# 0_3b.net
KiCad netlist of a schematic drawn in EAGLE
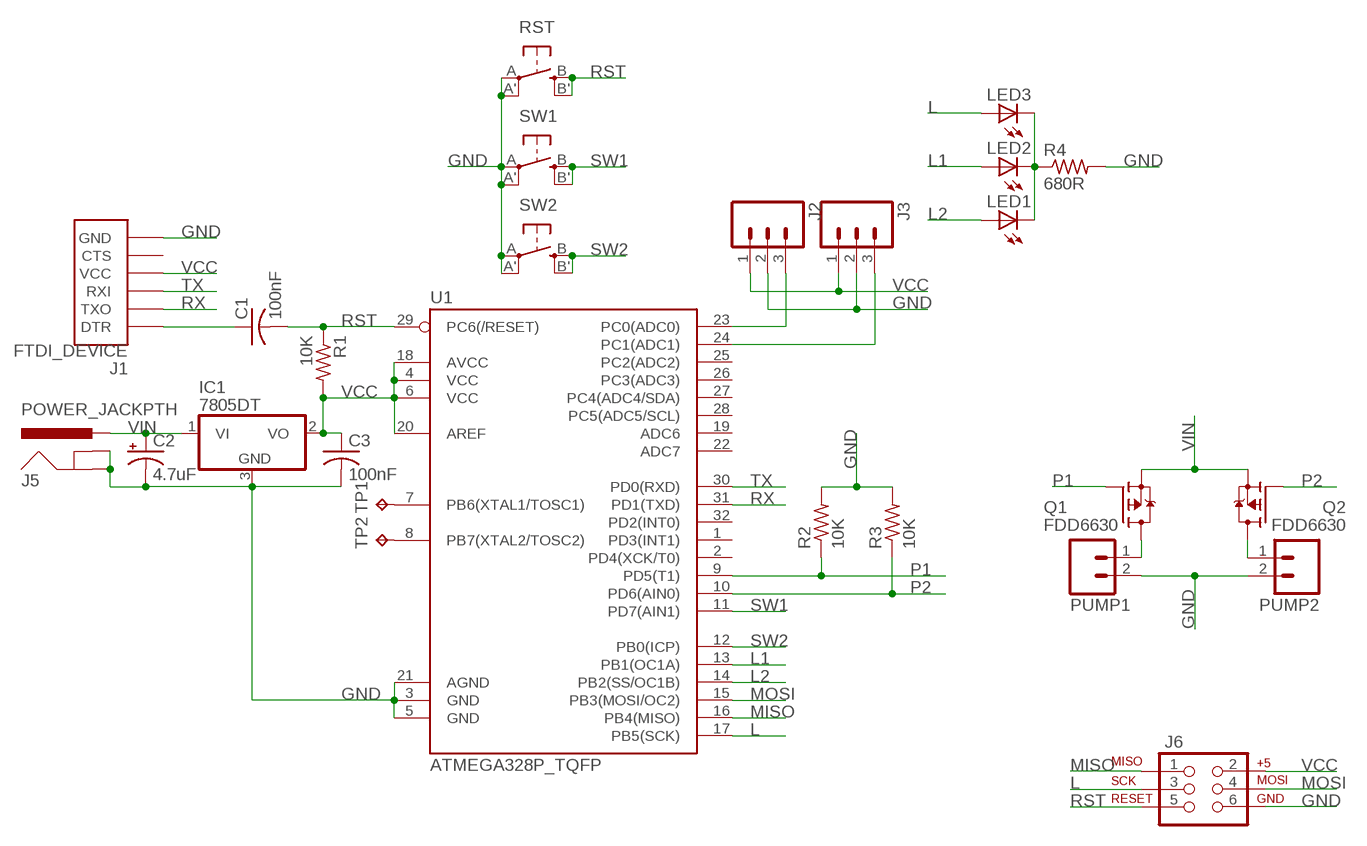
[diagram p0: schematic, sheet 1]

(export (version "E")
  (design (tool "Eeschema 10.0.6"))
  (components
    (comp (ref "C1")
      (value "100nF")
      (footprint "eagle-import:C1206K")
      (libsource (lib "eagle-import") (part "resistor_C-USC1206K"))
    )
    (comp (ref "C2")
      (value "4.7uF")
      (footprint "eagle-import:153CLV-0405")
      (libsource (lib "eagle-import") (part "CPOL-US153CLV-0405"))
    )
    (comp (ref "C3")
      (value "100nF")
      (footprint "eagle-import:C1206K")
      (libsource (lib "eagle-import") (part "C-USC1206K"))
    )
    (comp (ref "IC1")
      (value "7805DT")
      (footprint "eagle-import:TO252")
      (libsource (lib "eagle-import") (part "78DT05"))
    )
    (comp (ref "J1")
      (value "FTDI_DEVICE")
      (footprint "eagle-import:FTDI_DEVICE_SIDE")
      (libsource (lib "eagle-import") (part "FTDI_DEVICE"))
    )
    (comp (ref "J2")
      (value "M03PTH")
      (footprint "eagle-import:1X03")
      (libsource (lib "eagle-import") (part "M03PTH"))
    )
    (comp (ref "J3")
      (value "M03PTH")
      (footprint "eagle-import:1X03")
      (libsource (lib "eagle-import") (part "M03PTH"))
    )
    (comp (ref "J5")
      (value "POWER_JACKPTH")
      (footprint "eagle-import:POWER_JACK_PTH")
      (libsource (lib "eagle-import") (part "POWER_JACKPTH"))
    )
    (comp (ref "J6")
      (value "AVR_SPI_PRG_6PTH")
      (footprint "eagle-import:2X3")
      (libsource (lib "eagle-import") (part "AVR_SPI_PRG_6PTH"))
    )
    (comp (ref "LED1")
      (value "LED3MM")
      (footprint "eagle-import:LED3MM")
      (libsource (lib "eagle-import") (part "LED3MM"))
    )
    (comp (ref "LED2")
      (value "LED3MM")
      (footprint "eagle-import:LED3MM")
      (libsource (lib "eagle-import") (part "LED3MM"))
    )
    (comp (ref "LED3")
      (value "LED3MM")
      (footprint "eagle-import:LED3MM")
      (libsource (lib "eagle-import") (part "LED3MM"))
    )
    (comp (ref "PUMP1")
      (value "M02PTH")
      (footprint "eagle-import:1X02")
      (libsource (lib "eagle-import") (part "M02PTH"))
    )
    (comp (ref "PUMP2")
      (value "M02PTH")
      (footprint "eagle-import:1X02")
      (libsource (lib "eagle-import") (part "M02PTH"))
    )
    (comp (ref "Q1")
      (value "FDD6630")
      (footprint "eagle-import:TO252")
      (libsource (lib "eagle-import") (part "FDD4141TO252"))
    )
    (comp (ref "Q2")
      (value "FDD6630")
      (footprint "eagle-import:TO252")
      (libsource (lib "eagle-import") (part "FDD4141TO252"))
    )
    (comp (ref "R1")
      (value "10K")
      (footprint "eagle-import:M0805")
      (libsource (lib "eagle-import") (part "R-US_M0805"))
    )
    (comp (ref "R2")
      (value "10K")
      (footprint "eagle-import:M0805")
      (libsource (lib "eagle-import") (part "R-US_M0805"))
    )
    (comp (ref "R3")
      (value "10K")
      (footprint "eagle-import:M0805")
      (libsource (lib "eagle-import") (part "R-US_M0805"))
    )
    (comp (ref "R4")
      (value "680R")
      (footprint "eagle-import:M0805")
      (libsource (lib "eagle-import") (part "R-US_M0805"))
    )
    (comp (ref "RST")
      (value "SPST_TACT-EVQQ2")
      (footprint "eagle-import:EVQ-Q2")
      (libsource (lib "eagle-import") (part "SPST_TACT-EVQQ2"))
    )
    (comp (ref "SW1")
      (value "SPST_TACT-EVQQ2")
      (footprint "eagle-import:EVQ-Q2")
      (libsource (lib "eagle-import") (part "SPST_TACT-EVQQ2"))
    )
    (comp (ref "SW2")
      (value "SPST_TACT-EVQQ2")
      (footprint "eagle-import:EVQ-Q2")
      (libsource (lib "eagle-import") (part "SPST_TACT-EVQQ2"))
    )
    (comp (ref "TP1")
      (value "TPTP15SQ")
      (footprint "eagle-import:TP15SQ")
      (libsource (lib "eagle-import") (part "TPTP15SQ"))
    )
    (comp (ref "TP2")
      (value "TPTP15SQ")
      (footprint "eagle-import:TP15SQ")
      (libsource (lib "eagle-import") (part "TPTP15SQ"))
    )
    (comp (ref "U1")
      (value "ATMEGA328P_TQFP")
      (footprint "eagle-import:TQFP32-08")
      (libsource (lib "eagle-import") (part "ATMEGA328P_TQFP"))
    )
  )
  (nets
    (net (code "1") (name "/GND") (class "Default")
      (node (ref "C2") (pin "-") (pinfunction "-_-") (pintype "passive"))
      (node (ref "C3") (pin "2") (pinfunction "2_2") (pintype "passive"))
      (node (ref "IC1") (pin "3") (pinfunction "GND_3") (pintype "passive"))
      (node (ref "J1") (pin "P$6") (pinfunction "GND_P$6") (pintype "bidirectional"))
      (node (ref "J2") (pin "2") (pinfunction "2_2") (pintype "passive"))
      (node (ref "J3") (pin "2") (pinfunction "2_2") (pintype "passive"))
      (node (ref "J5") (pin "GND") (pinfunction "GND_GND") (pintype "bidirectional"))
      (node (ref "J5") (pin "GNDBREAK") (pinfunction "GNDBREAK_GNDBREAK") (pintype "bidirectional"))
      (node (ref "J6") (pin "6") (pinfunction "6_6") (pintype "passive"))
      (node (ref "PUMP1") (pin "2") (pinfunction "2_2") (pintype "passive"))
      (node (ref "PUMP2") (pin "2") (pinfunction "2_2") (pintype "passive"))
      (node (ref "R2") (pin "2") (pinfunction "2_2") (pintype "passive"))
      (node (ref "R3") (pin "2") (pinfunction "2_2") (pintype "passive"))
      (node (ref "R4") (pin "2") (pinfunction "2_2") (pintype "passive"))
      (node (ref "RST") (pin "A") (pinfunction "P_A") (pintype "passive"))
      (node (ref "RST") (pin "A'") (pinfunction "P1_A'") (pintype "passive"))
      (node (ref "SW1") (pin "A") (pinfunction "P_A") (pintype "passive"))
      (node (ref "SW1") (pin "A'") (pinfunction "P1_A'") (pintype "passive"))
      (node (ref "SW2") (pin "A") (pinfunction "P_A") (pintype "passive"))
      (node (ref "SW2") (pin "A'") (pinfunction "P1_A'") (pintype "passive"))
      (node (ref "U1") (pin "21") (pinfunction "AGND_21") (pintype "bidirectional"))
      (node (ref "U1") (pin "3") (pinfunction "GND_3") (pintype "bidirectional"))
      (node (ref "U1") (pin "5") (pinfunction "GND_5") (pintype "bidirectional"))
    )
    (net (code "2") (name "/L") (class "Default")
      (node (ref "J6") (pin "3") (pinfunction "3_3") (pintype "passive"))
      (node (ref "LED3") (pin "A") (pinfunction "A_A") (pintype "passive"))
      (node (ref "U1") (pin "17") (pinfunction "PB5(SCK)_17") (pintype "bidirectional"))
    )
    (net (code "3") (name "/L1") (class "Default")
      (node (ref "LED2") (pin "A") (pinfunction "A_A") (pintype "passive"))
      (node (ref "U1") (pin "13") (pinfunction "PB1(OC1A)_13") (pintype "bidirectional"))
    )
    (net (code "4") (name "/L2") (class "Default")
      (node (ref "LED1") (pin "A") (pinfunction "A_A") (pintype "passive"))
      (node (ref "U1") (pin "14") (pinfunction "PB2(SS/OC1B)_14") (pintype "bidirectional"))
    )
    (net (code "5") (name "/MISO") (class "Default")
      (node (ref "J6") (pin "1") (pinfunction "1_1") (pintype "passive"))
      (node (ref "U1") (pin "16") (pinfunction "PB4(MISO)_16") (pintype "bidirectional"))
    )
    (net (code "6") (name "/MOSI") (class "Default")
      (node (ref "J6") (pin "4") (pinfunction "4_4") (pintype "passive"))
      (node (ref "U1") (pin "15") (pinfunction "PB3(MOSI/OC2)_15") (pintype "bidirectional"))
    )
    (net (code "7") (name "/P1") (class "Default")
      (node (ref "Q1") (pin "1") (pinfunction "G_1") (pintype "passive"))
      (node (ref "R2") (pin "1") (pinfunction "1_1") (pintype "passive"))
      (node (ref "U1") (pin "9") (pinfunction "PD5(T1)_9") (pintype "bidirectional"))
    )
    (net (code "8") (name "/P2") (class "Default")
      (node (ref "Q2") (pin "1") (pinfunction "G_1") (pintype "passive"))
      (node (ref "R3") (pin "1") (pinfunction "1_1") (pintype "passive"))
      (node (ref "U1") (pin "10") (pinfunction "PD6(AIN0)_10") (pintype "bidirectional"))
    )
    (net (code "9") (name "/RST") (class "Default")
      (node (ref "C1") (pin "2") (pinfunction "2_2") (pintype "passive"))
      (node (ref "J6") (pin "5") (pinfunction "5_5") (pintype "passive"))
      (node (ref "R1") (pin "1") (pinfunction "1_1") (pintype "passive"))
      (node (ref "RST") (pin "B") (pinfunction "S_B") (pintype "passive"))
      (node (ref "RST") (pin "B'") (pinfunction "S1_B'") (pintype "passive"))
      (node (ref "U1") (pin "29") (pinfunction "PC6(/RESET)_29") (pintype "bidirectional"))
    )
    (net (code "10") (name "/RX") (class "Default")
      (node (ref "J1") (pin "P$2") (pinfunction "TXO_P$2") (pintype "bidirectional"))
      (node (ref "U1") (pin "31") (pinfunction "PD1(TXD)_31") (pintype "bidirectional"))
    )
    (net (code "11") (name "/SW1") (class "Default")
      (node (ref "SW1") (pin "B") (pinfunction "S_B") (pintype "passive"))
      (node (ref "SW1") (pin "B'") (pinfunction "S1_B'") (pintype "passive"))
      (node (ref "U1") (pin "11") (pinfunction "PD7(AIN1)_11") (pintype "bidirectional"))
    )
    (net (code "12") (name "/SW2") (class "Default")
      (node (ref "SW2") (pin "B") (pinfunction "S_B") (pintype "passive"))
      (node (ref "SW2") (pin "B'") (pinfunction "S1_B'") (pintype "passive"))
      (node (ref "U1") (pin "12") (pinfunction "PB0(ICP)_12") (pintype "bidirectional"))
    )
    (net (code "13") (name "/TX") (class "Default")
      (node (ref "J1") (pin "P$3") (pinfunction "RXI_P$3") (pintype "bidirectional"))
      (node (ref "U1") (pin "30") (pinfunction "PD0(RXD)_30") (pintype "bidirectional"))
    )
    (net (code "14") (name "/VCC") (class "Default")
      (node (ref "C3") (pin "1") (pinfunction "1_1") (pintype "passive"))
      (node (ref "IC1") (pin "2") (pinfunction "VO_2") (pintype "passive"))
      (node (ref "J1") (pin "P$4") (pinfunction "VCC_P$4") (pintype "bidirectional"))
      (node (ref "J2") (pin "1") (pinfunction "1_1") (pintype "passive"))
      (node (ref "J3") (pin "1") (pinfunction "1_1") (pintype "passive"))
      (node (ref "J6") (pin "2") (pinfunction "2_2") (pintype "passive"))
      (node (ref "R1") (pin "2") (pinfunction "2_2") (pintype "passive"))
      (node (ref "U1") (pin "18") (pinfunction "AVCC_18") (pintype "bidirectional"))
      (node (ref "U1") (pin "20") (pinfunction "AREF_20") (pintype "bidirectional"))
      (node (ref "U1") (pin "4") (pinfunction "VCC_4") (pintype "bidirectional"))
      (node (ref "U1") (pin "6") (pinfunction "VCC_6") (pintype "bidirectional"))
    )
    (net (code "15") (name "/VIN") (class "Default")
      (node (ref "C2") (pin "+") (pinfunction "+_+") (pintype "passive"))
      (node (ref "IC1") (pin "1") (pinfunction "VI_1") (pintype "input"))
      (node (ref "J5") (pin "PWR") (pinfunction "PWR_PWR") (pintype "bidirectional"))
      (node (ref "Q1") (pin "2") (pinfunction "S_2") (pintype "passive"))
      (node (ref "Q2") (pin "2") (pinfunction "S_2") (pintype "passive"))
    )
    (net (code "16") (name "Net-(J1-DTR)") (class "Default")
      (node (ref "C1") (pin "1") (pinfunction "1_1") (pintype "passive"))
      (node (ref "J1") (pin "P$1") (pinfunction "DTR_P$1") (pintype "bidirectional"))
    )
    (net (code "17") (name "Net-(LED1-C)") (class "Default")
      (node (ref "LED1") (pin "K") (pinfunction "C_K") (pintype "passive"))
      (node (ref "LED2") (pin "K") (pinfunction "C_K") (pintype "passive"))
      (node (ref "LED3") (pin "K") (pinfunction "C_K") (pintype "passive"))
      (node (ref "R4") (pin "1") (pinfunction "1_1") (pintype "passive"))
    )
    (net (code "18") (name "Net-(Q1-D)") (class "Default")
      (node (ref "PUMP1") (pin "1") (pinfunction "1_1") (pintype "passive"))
      (node (ref "Q1") (pin "3") (pinfunction "D_3") (pintype "passive"))
    )
    (net (code "19") (name "Net-(Q2-D)") (class "Default")
      (node (ref "PUMP2") (pin "1") (pinfunction "1_1") (pintype "passive"))
      (node (ref "Q2") (pin "3") (pinfunction "D_3") (pintype "passive"))
    )
    (net (code "20") (name "Net-(U1-PB6(XTAL1{slash}TOSC1))") (class "Default")
      (node (ref "TP1") (pin "TP") (pinfunction "TP_TP") (pintype "input"))
      (node (ref "U1") (pin "7") (pinfunction "PB6(XTAL1/TOSC1)_7") (pintype "bidirectional"))
    )
    (net (code "21") (name "Net-(U1-PB7(XTAL2{slash}TOSC2))") (class "Default")
      (node (ref "TP2") (pin "TP") (pinfunction "TP_TP") (pintype "input"))
      (node (ref "U1") (pin "8") (pinfunction "PB7(XTAL2/TOSC2)_8") (pintype "bidirectional"))
    )
    (net (code "22") (name "Net-(U1-PC0(ADC0))") (class "Default")
      (node (ref "J2") (pin "3") (pinfunction "3_3") (pintype "passive"))
      (node (ref "U1") (pin "23") (pinfunction "PC0(ADC0)_23") (pintype "bidirectional"))
    )
    (net (code "23") (name "Net-(U1-PC1(ADC1))") (class "Default")
      (node (ref "J3") (pin "3") (pinfunction "3_3") (pintype "passive"))
      (node (ref "U1") (pin "24") (pinfunction "PC1(ADC1)_24") (pintype "bidirectional"))
    )
    (net (code "24") (name "unconnected-(J1-CTS-PadP$5)") (class "Default")
      (node (ref "J1") (pin "P$5") (pinfunction "CTS_P$5") (pintype "bidirectional"))
    )
    (net (code "25") (name "unconnected-(U1-ADC6-Pad19)") (class "Default")
      (node (ref "U1") (pin "19") (pinfunction "ADC6_19") (pintype "bidirectional"))
    )
    (net (code "26") (name "unconnected-(U1-ADC7-Pad22)") (class "Default")
      (node (ref "U1") (pin "22") (pinfunction "ADC7_22") (pintype "bidirectional"))
    )
    (net (code "27") (name "unconnected-(U1-PC2(ADC2)-Pad25)") (class "Default")
      (node (ref "U1") (pin "25") (pinfunction "PC2(ADC2)_25") (pintype "bidirectional"))
    )
    (net (code "28") (name "unconnected-(U1-PC3(ADC3)-Pad26)") (class "Default")
      (node (ref "U1") (pin "26") (pinfunction "PC3(ADC3)_26") (pintype "bidirectional"))
    )
    (net (code "29") (name "unconnected-(U1-PC4(ADC4{slash}SDA)-Pad27)") (class "Default")
      (node (ref "U1") (pin "27") (pinfunction "PC4(ADC4/SDA)_27") (pintype "bidirectional"))
    )
    (net (code "30") (name "unconnected-(U1-PC5(ADC5{slash}SCL)-Pad28)") (class "Default")
      (node (ref "U1") (pin "28") (pinfunction "PC5(ADC5/SCL)_28") (pintype "bidirectional"))
    )
    (net (code "31") (name "unconnected-(U1-PD2(INT0)-Pad32)") (class "Default")
      (node (ref "U1") (pin "32") (pinfunction "PD2(INT0)_32") (pintype "bidirectional"))
    )
    (net (code "32") (name "unconnected-(U1-PD3(INT1)-Pad1)") (class "Default")
      (node (ref "U1") (pin "1") (pinfunction "PD3(INT1)_1") (pintype "bidirectional"))
    )
    (net (code "33") (name "unconnected-(U1-PD4(XCK{slash}T0)-Pad2)") (class "Default")
      (node (ref "U1") (pin "2") (pinfunction "PD4(XCK/T0)_2") (pintype "bidirectional"))
    )
  )
)
